# schematic.net
KiCad netlist of a schematic drawn in Altium Designer
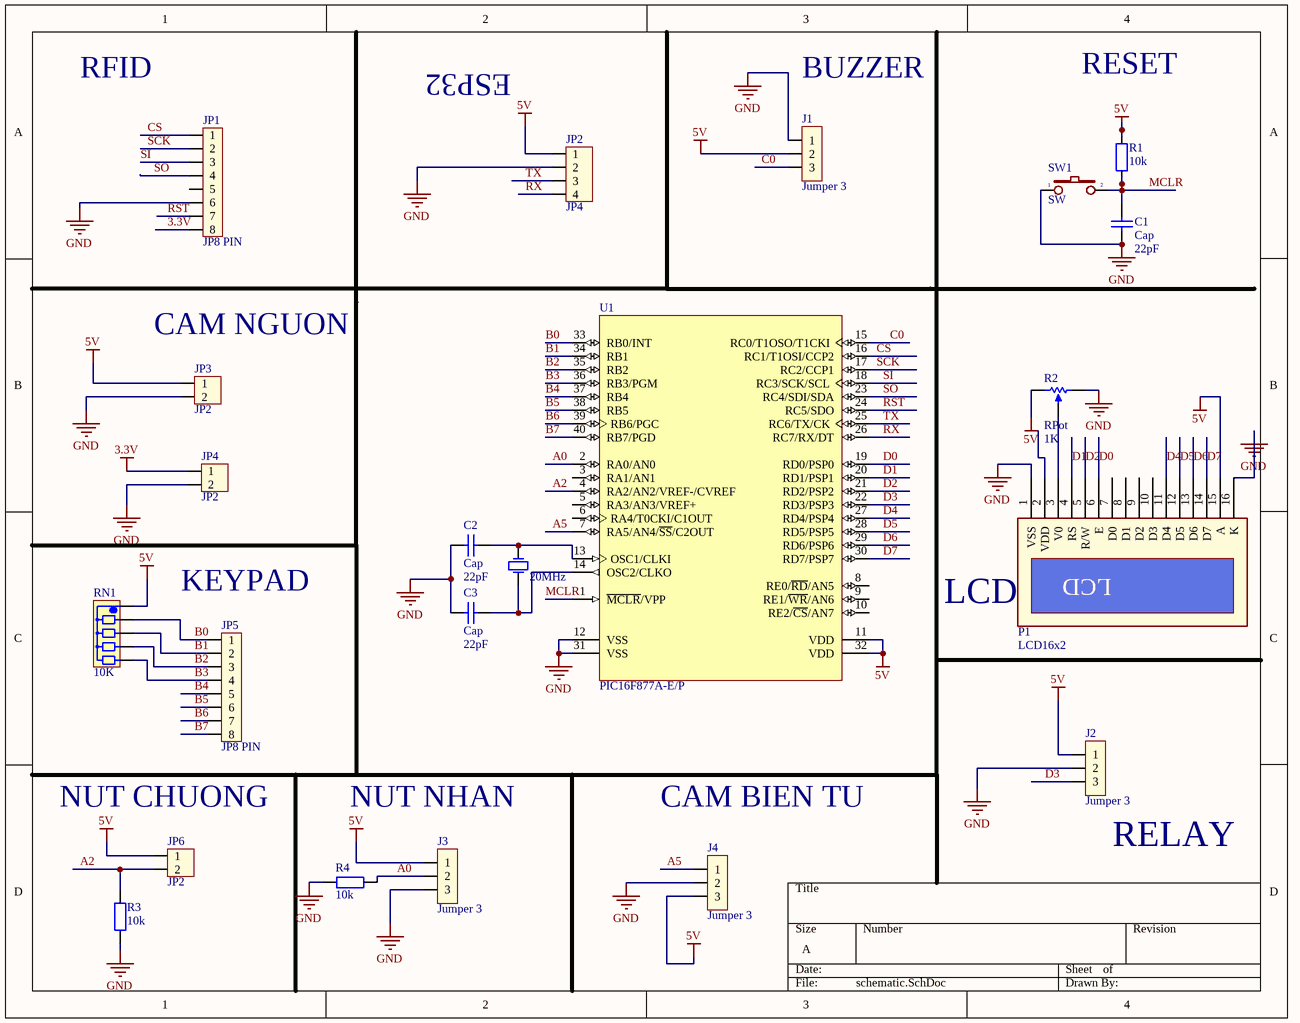
[diagram p0: schematic.SchDoc]

(export (version "E")
  (design (tool "Eeschema 10.0.6"))
  (components
    (comp (ref "C1")
      (value "Cap")
      (footprint "RAD-0.3")
      (description "Capacitor")
      (fields (field (name "ALTIUM_VALUE") "22pF") (field (name "PUBLISHER") "Altium Limited"))
      (libsource (lib "Miscellaneous Devices") (part "Cap"))
    )
    (comp (ref "C2")
      (value "Cap")
      (footprint "RAD-0.3")
      (description "Capacitor")
      (fields (field (name "ALTIUM_VALUE") "22pF") (field (name "PUBLISHER") "Altium Limited"))
      (libsource (lib "Miscellaneous Devices") (part "Cap"))
    )
    (comp (ref "C3")
      (value "Cap")
      (footprint "RAD-0.3")
      (description "Capacitor")
      (fields (field (name "ALTIUM_VALUE") "22pF") (field (name "PUBLISHER") "Altium Limited"))
      (libsource (lib "Miscellaneous Devices") (part "Cap"))
    )
    (comp (ref "J1") (value "Jumper 3") (footprint "JP3") (libsource (lib "My Library") (part "JP3")))
    (comp (ref "J2") (value "Jumper 3") (footprint "JP3") (libsource (lib "My Library") (part "JP3")))
    (comp (ref "J3") (value "Jumper 3") (footprint "JP3") (libsource (lib "My Library") (part "JP3")))
    (comp (ref "J4") (value "Jumper 3") (footprint "JP3") (libsource (lib "My Library") (part "JP3")))
    (comp (ref "JP1") (value "JP8 PIN") (footprint "JP8") (libsource (lib "My Library") (part "JP8")))
    (comp (ref "JP2")
      (value "JP4")
      (footprint "CON4")
      (description "Connector 4")
      (libsource (lib "My Library") (part "Con4"))
    )
    (comp (ref "JP3")
      (value "JP2")
      (footprint "CON2")
      (description "Connector 2")
      (libsource (lib "My Library") (part "Con2"))
    )
    (comp (ref "JP4")
      (value "JP2")
      (footprint "CON2")
      (description "Connector 2")
      (libsource (lib "My Library") (part "Con2"))
    )
    (comp (ref "JP5") (value "JP8 PIN") (footprint "JP8") (libsource (lib "My Library") (part "JP8")))
    (comp (ref "JP6")
      (value "JP2")
      (footprint "CON2")
      (description "Connector 2")
      (libsource (lib "My Library") (part "Con2"))
    )
    (comp (ref "P1") (value "LCD16x2") (footprint "LCD16X2") (libsource (lib "My Library") (part "LCD Text")))
    (comp (ref "R1")
      (value "10k")
      (footprint "RES-1/4W")
      (description "Dán")
      (libsource (lib "THU VIEN SCH") (part "Tro 0603 1% 10k"))
    )
    (comp (ref "R2")
      (value "RPot")
      (footprint "VR5")
      (description "Potentiometer")
      (fields (field (name "ALTIUM_VALUE") "1K") (field (name "PUBLISHER") "Altium Limited"))
      (libsource (lib "Miscellaneous Devices") (part "RPot"))
    )
    (comp (ref "R3")
      (value "10k")
      (footprint "RES-1/4W")
      (description "Dán")
      (libsource (lib "THU VIEN SCH") (part "Tro 0603 1% 10k"))
    )
    (comp (ref "R4")
      (value "10k")
      (footprint "RES-1/4W")
      (description "Dán")
      (libsource (lib "THU VIEN SCH") (part "Tro 0603 1% 10k"))
    )
    (comp (ref "RN1")
      (value "10K")
      (footprint "RN4")
      (description "Resistor 4 (thanh)")
      (libsource (lib "syhaunguyen") (part "RN4"))
    )
    (comp (ref "SW1")
      (value "SW")
      (footprint "SW2")
      (description "Switch button 2 pin")
      (libsource (lib "syhaunguyen") (part "SW2"))
    )
    (comp (ref "U1")
      (value "PIC16F877A-E/P")
      (footprint "DIP.100/40/W.600/L2.100")
      (fields (field (name "PUBLISHER") "Altium Limited"))
      (libsource (lib "My Library") (part "PIC16F877A-E/P"))
    )
    (comp (ref "Y1")
      (value "20MHz")
      (footprint "XTAL")
      (description "Crystal Oscillator")
      (fields (field (name "PUBLISHER") "Altium Limited"))
      (libsource (lib "My Library") (part "XTAL"))
    )
  )
  (nets
    (net (code "1") (name "/A0") (class "Default")
      (node (ref "J3") (pin "2") (pinfunction "2_2") (pintype "passive"))
      (node (ref "R4") (pin "1") (pinfunction "1_1") (pintype "passive"))
      (node (ref "U1") (pin "2") (pinfunction "RA0/AN0_2") (pintype "bidirectional"))
    )
    (net (code "2") (name "/A2") (class "Default")
      (node (ref "JP6") (pin "2") (pinfunction "2_2") (pintype "passive"))
      (node (ref "R3") (pin "2") (pinfunction "2_2") (pintype "passive"))
      (node (ref "U1") (pin "4") (pinfunction "RA2/AN2/VREF-/CVREF_4") (pintype "bidirectional"))
    )
    (net (code "3") (name "/A5") (class "Default")
      (node (ref "J4") (pin "1") (pinfunction "1_1") (pintype "passive"))
      (node (ref "U1") (pin "7") (pinfunction "RA5/AN4/~{SS}/C2OUT_7") (pintype "bidirectional"))
    )
    (net (code "4") (name "/B0") (class "Default")
      (node (ref "JP5") (pin "1") (pinfunction "1_1") (pintype "passive"))
      (node (ref "RN1") (pin "2") (pinfunction "2_2") (pintype "passive"))
      (node (ref "U1") (pin "33") (pinfunction "RB0/INT_33") (pintype "bidirectional"))
    )
    (net (code "5") (name "/B1") (class "Default")
      (node (ref "JP5") (pin "2") (pinfunction "2_2") (pintype "passive"))
      (node (ref "RN1") (pin "3") (pinfunction "3_3") (pintype "passive"))
      (node (ref "U1") (pin "34") (pinfunction "RB1_34") (pintype "bidirectional"))
    )
    (net (code "6") (name "/B2") (class "Default")
      (node (ref "JP5") (pin "3") (pinfunction "3_3") (pintype "passive"))
      (node (ref "RN1") (pin "4") (pinfunction "4_4") (pintype "passive"))
      (node (ref "U1") (pin "35") (pinfunction "RB2_35") (pintype "bidirectional"))
    )
    (net (code "7") (name "/B3") (class "Default")
      (node (ref "JP5") (pin "4") (pinfunction "4_4") (pintype "passive"))
      (node (ref "RN1") (pin "5") (pinfunction "5_5") (pintype "passive"))
      (node (ref "U1") (pin "36") (pinfunction "RB3/PGM_36") (pintype "bidirectional"))
    )
    (net (code "8") (name "/B4") (class "Default")
      (node (ref "JP5") (pin "5") (pinfunction "5_5") (pintype "passive"))
      (node (ref "U1") (pin "37") (pinfunction "RB4_37") (pintype "bidirectional"))
    )
    (net (code "9") (name "/B5") (class "Default")
      (node (ref "JP5") (pin "6") (pinfunction "6_6") (pintype "passive"))
      (node (ref "U1") (pin "38") (pinfunction "RB5_38") (pintype "bidirectional"))
    )
    (net (code "10") (name "/B6") (class "Default")
      (node (ref "JP5") (pin "7") (pinfunction "7_7") (pintype "passive"))
      (node (ref "U1") (pin "39") (pinfunction "RB6/PGC_39") (pintype "bidirectional"))
    )
    (net (code "11") (name "/B7") (class "Default")
      (node (ref "JP5") (pin "8") (pinfunction "8_8") (pintype "passive"))
      (node (ref "U1") (pin "40") (pinfunction "RB7/PGD_40") (pintype "bidirectional"))
    )
    (net (code "12") (name "/C0") (class "Default")
      (node (ref "J1") (pin "3") (pinfunction "3_3") (pintype "passive"))
      (node (ref "U1") (pin "15") (pinfunction "RC0/T1OSO/T1CKI_15") (pintype "bidirectional"))
    )
    (net (code "13") (name "/CS") (class "Default")
      (node (ref "JP1") (pin "1") (pinfunction "1_1") (pintype "passive"))
      (node (ref "U1") (pin "16") (pinfunction "RC1/T1OSI/CCP2_16") (pintype "bidirectional"))
    )
    (net (code "14") (name "/D0") (class "Default")
      (node (ref "P1") (pin "6") (pinfunction "E_6") (pintype "passive"))
      (node (ref "U1") (pin "19") (pinfunction "RD0/PSP0_19") (pintype "bidirectional"))
    )
    (net (code "15") (name "/D1") (class "Default")
      (node (ref "P1") (pin "4") (pinfunction "RS_4") (pintype "passive"))
      (node (ref "U1") (pin "20") (pinfunction "RD1/PSP1_20") (pintype "bidirectional"))
    )
    (net (code "16") (name "/D2") (class "Default")
      (node (ref "P1") (pin "5") (pinfunction "R/W_5") (pintype "passive"))
      (node (ref "U1") (pin "21") (pinfunction "RD2/PSP2_21") (pintype "bidirectional"))
    )
    (net (code "17") (name "/D3") (class "Default")
      (node (ref "J2") (pin "3") (pinfunction "3_3") (pintype "passive"))
      (node (ref "U1") (pin "22") (pinfunction "RD3/PSP3_22") (pintype "bidirectional"))
    )
    (net (code "18") (name "/D4") (class "Default")
      (node (ref "P1") (pin "11") (pinfunction "D4_11") (pintype "passive"))
      (node (ref "U1") (pin "27") (pinfunction "RD4/PSP4_27") (pintype "bidirectional"))
    )
    (net (code "19") (name "/D5") (class "Default")
      (node (ref "P1") (pin "12") (pinfunction "D5_12") (pintype "passive"))
      (node (ref "U1") (pin "28") (pinfunction "RD5/PSP5_28") (pintype "bidirectional"))
    )
    (net (code "20") (name "/D6") (class "Default")
      (node (ref "P1") (pin "13") (pinfunction "D6_13") (pintype "passive"))
      (node (ref "U1") (pin "29") (pinfunction "RD6/PSP6_29") (pintype "bidirectional"))
    )
    (net (code "21") (name "/D7") (class "Default")
      (node (ref "P1") (pin "14") (pinfunction "D7_14") (pintype "passive"))
      (node (ref "U1") (pin "30") (pinfunction "RD7/PSP7_30") (pintype "bidirectional"))
    )
    (net (code "22") (name "/MCLR") (class "Default")
      (node (ref "C1") (pin "2") (pinfunction "2_2") (pintype "passive"))
      (node (ref "R1") (pin "1") (pinfunction "1_1") (pintype "passive"))
      (node (ref "SW1") (pin "2") (pinfunction "2_2") (pintype "passive"))
      (node (ref "U1") (pin "1") (pinfunction "~{MCLR}/VPP_1") (pintype "input"))
    )
    (net (code "23") (name "/RST") (class "Default")
      (node (ref "JP1") (pin "7") (pinfunction "7_7") (pintype "passive"))
      (node (ref "U1") (pin "24") (pinfunction "RC5/SDO_24") (pintype "bidirectional"))
    )
    (net (code "24") (name "/RX") (class "Default")
      (node (ref "JP2") (pin "4") (pinfunction "4_4") (pintype "passive"))
      (node (ref "U1") (pin "26") (pinfunction "RC7/RX/DT_26") (pintype "bidirectional"))
    )
    (net (code "25") (name "/SCK") (class "Default")
      (node (ref "JP1") (pin "2") (pinfunction "2_2") (pintype "passive"))
      (node (ref "U1") (pin "17") (pinfunction "RC2/CCP1_17") (pintype "bidirectional"))
    )
    (net (code "26") (name "/SI") (class "Default")
      (node (ref "JP1") (pin "3") (pinfunction "3_3") (pintype "passive"))
      (node (ref "U1") (pin "18") (pinfunction "RC3/SCK/SCL_18") (pintype "bidirectional"))
    )
    (net (code "27") (name "/SO") (class "Default")
      (node (ref "JP1") (pin "4") (pinfunction "4_4") (pintype "passive"))
      (node (ref "U1") (pin "23") (pinfunction "RC4/SDI/SDA_23") (pintype "bidirectional"))
    )
    (net (code "28") (name "/TX") (class "Default")
      (node (ref "JP2") (pin "3") (pinfunction "3_3") (pintype "passive"))
      (node (ref "U1") (pin "25") (pinfunction "RC6/TX/CK_25") (pintype "bidirectional"))
    )
    (net (code "29") (name "3.3V") (class "Default")
      (node (ref "JP1") (pin "8") (pinfunction "8_8") (pintype "passive"))
      (node (ref "JP4") (pin "1") (pinfunction "1_1") (pintype "passive"))
    )
    (net (code "30") (name "5V") (class "Default")
      (node (ref "J1") (pin "2") (pinfunction "2_2") (pintype "passive"))
      (node (ref "J2") (pin "1") (pinfunction "1_1") (pintype "passive"))
      (node (ref "J3") (pin "1") (pinfunction "1_1") (pintype "passive"))
      (node (ref "J4") (pin "3") (pinfunction "3_3") (pintype "passive"))
      (node (ref "JP2") (pin "1") (pinfunction "1_1") (pintype "passive"))
      (node (ref "JP3") (pin "1") (pinfunction "1_1") (pintype "passive"))
      (node (ref "JP6") (pin "1") (pinfunction "1_1") (pintype "passive"))
      (node (ref "P1") (pin "15") (pinfunction "A_15") (pintype "passive"))
      (node (ref "R1") (pin "2") (pinfunction "2_2") (pintype "passive"))
      (node (ref "R2") (pin "1") (pinfunction "TOP_1") (pintype "passive"))
      (node (ref "RN1") (pin "1") (pinfunction "1_1") (pintype "passive"))
      (node (ref "U1") (pin "11") (pinfunction "VDD_11") (pintype "power_in"))
      (node (ref "U1") (pin "32") (pinfunction "VDD_32") (pintype "power_in"))
    )
    (net (code "31") (name "GND") (class "Default")
      (node (ref "C1") (pin "1") (pinfunction "1_1") (pintype "passive"))
      (node (ref "C2") (pin "1") (pinfunction "1_1") (pintype "passive"))
      (node (ref "C3") (pin "1") (pinfunction "1_1") (pintype "passive"))
      (node (ref "J1") (pin "1") (pinfunction "1_1") (pintype "passive"))
      (node (ref "J2") (pin "2") (pinfunction "2_2") (pintype "passive"))
      (node (ref "J3") (pin "3") (pinfunction "3_3") (pintype "passive"))
      (node (ref "J4") (pin "2") (pinfunction "2_2") (pintype "passive"))
      (node (ref "JP1") (pin "6") (pinfunction "6_6") (pintype "passive"))
      (node (ref "JP2") (pin "2") (pinfunction "2_2") (pintype "passive"))
      (node (ref "JP3") (pin "2") (pinfunction "2_2") (pintype "passive"))
      (node (ref "JP4") (pin "2") (pinfunction "2_2") (pintype "passive"))
      (node (ref "P1") (pin "1") (pinfunction "VSS_1") (pintype "passive"))
      (node (ref "P1") (pin "16") (pinfunction "K_16") (pintype "passive"))
      (node (ref "R2") (pin "2") (pinfunction "BOT_2") (pintype "passive"))
      (node (ref "R3") (pin "1") (pinfunction "1_1") (pintype "passive"))
      (node (ref "R4") (pin "2") (pinfunction "2_2") (pintype "passive"))
      (node (ref "SW1") (pin "1") (pinfunction "1_1") (pintype "passive"))
      (node (ref "U1") (pin "12") (pinfunction "VSS_12") (pintype "power_in"))
      (node (ref "U1") (pin "31") (pinfunction "VSS_31") (pintype "power_in"))
    )
    (net (code "32") (name "Net-(P1-V0)") (class "Default")
      (node (ref "P1") (pin "3") (pinfunction "V0_3") (pintype "passive"))
      (node (ref "R2") (pin "3") (pinfunction "TAP_3") (pintype "passive"))
    )
    (net (code "33") (name "Net-(U1-OSC1{slash}CLKI)") (class "Default")
      (node (ref "C2") (pin "2") (pinfunction "2_2") (pintype "passive"))
      (node (ref "U1") (pin "13") (pinfunction "OSC1/CLKI_13") (pintype "input"))
      (node (ref "Y1") (pin "2") (pinfunction "OSC2_2") (pintype "passive"))
    )
    (net (code "34") (name "Net-(U1-OSC2{slash}CLKO)") (class "Default")
      (node (ref "C3") (pin "2") (pinfunction "2_2") (pintype "passive"))
      (node (ref "U1") (pin "14") (pinfunction "OSC2/CLKO_14") (pintype "output"))
      (node (ref "Y1") (pin "1") (pinfunction "OSC1_1") (pintype "passive"))
    )
    (net (code "35") (name "unconnected-(JP1-Pad5)") (class "Default")
      (node (ref "JP1") (pin "5") (pinfunction "5_5") (pintype "passive"))
    )
    (net (code "36") (name "unconnected-(P1-D0-Pad7)") (class "Default")
      (node (ref "P1") (pin "7") (pinfunction "D0_7") (pintype "passive"))
    )
    (net (code "37") (name "unconnected-(P1-D1-Pad8)") (class "Default")
      (node (ref "P1") (pin "8") (pinfunction "D1_8") (pintype "passive"))
    )
    (net (code "38") (name "unconnected-(P1-D2-Pad9)") (class "Default")
      (node (ref "P1") (pin "9") (pinfunction "D2_9") (pintype "passive"))
    )
    (net (code "39") (name "unconnected-(P1-D3-Pad10)") (class "Default")
      (node (ref "P1") (pin "10") (pinfunction "D3_10") (pintype "passive"))
    )
    (net (code "40") (name "unconnected-(P1-VDD-Pad2)") (class "Default")
      (node (ref "P1") (pin "2") (pinfunction "VDD_2") (pintype "passive"))
    )
    (net (code "41") (name "unconnected-(U1-RA1{slash}AN1-Pad3)") (class "Default")
      (node (ref "U1") (pin "3") (pinfunction "RA1/AN1_3") (pintype "bidirectional"))
    )
    (net (code "42") (name "unconnected-(U1-RA3{slash}AN3{slash}VREF+-Pad5)") (class "Default")
      (node (ref "U1") (pin "5") (pinfunction "RA3/AN3/VREF+_5") (pintype "bidirectional"))
    )
    (net (code "43") (name "unconnected-(U1-RA4{slash}T0CKI{slash}C1OUT-Pad6)") (class "Default")
      (node (ref "U1") (pin "6") (pinfunction "RA4/T0CKI/C1OUT_6") (pintype "bidirectional"))
    )
    (net (code "44") (name "unconnected-(U1-RE0{slash}~{RD}{slash}AN5-Pad8)") (class "Default")
      (node (ref "U1") (pin "8") (pinfunction "RE0/~{RD}/AN5_8") (pintype "bidirectional"))
    )
    (net (code "45") (name "unconnected-(U1-RE1{slash}~{WR}{slash}AN6-Pad9)") (class "Default")
      (node (ref "U1") (pin "9") (pinfunction "RE1/~{WR}/AN6_9") (pintype "bidirectional"))
    )
    (net (code "46") (name "unconnected-(U1-RE2{slash}~{CS}{slash}AN7-Pad10)") (class "Default")
      (node (ref "U1") (pin "10") (pinfunction "RE2/~{CS}/AN7_10") (pintype "bidirectional"))
    )
  )
)
